# RadarControl_V1_00.net
KiCad netlist of a schematic drawn in Altium Designer
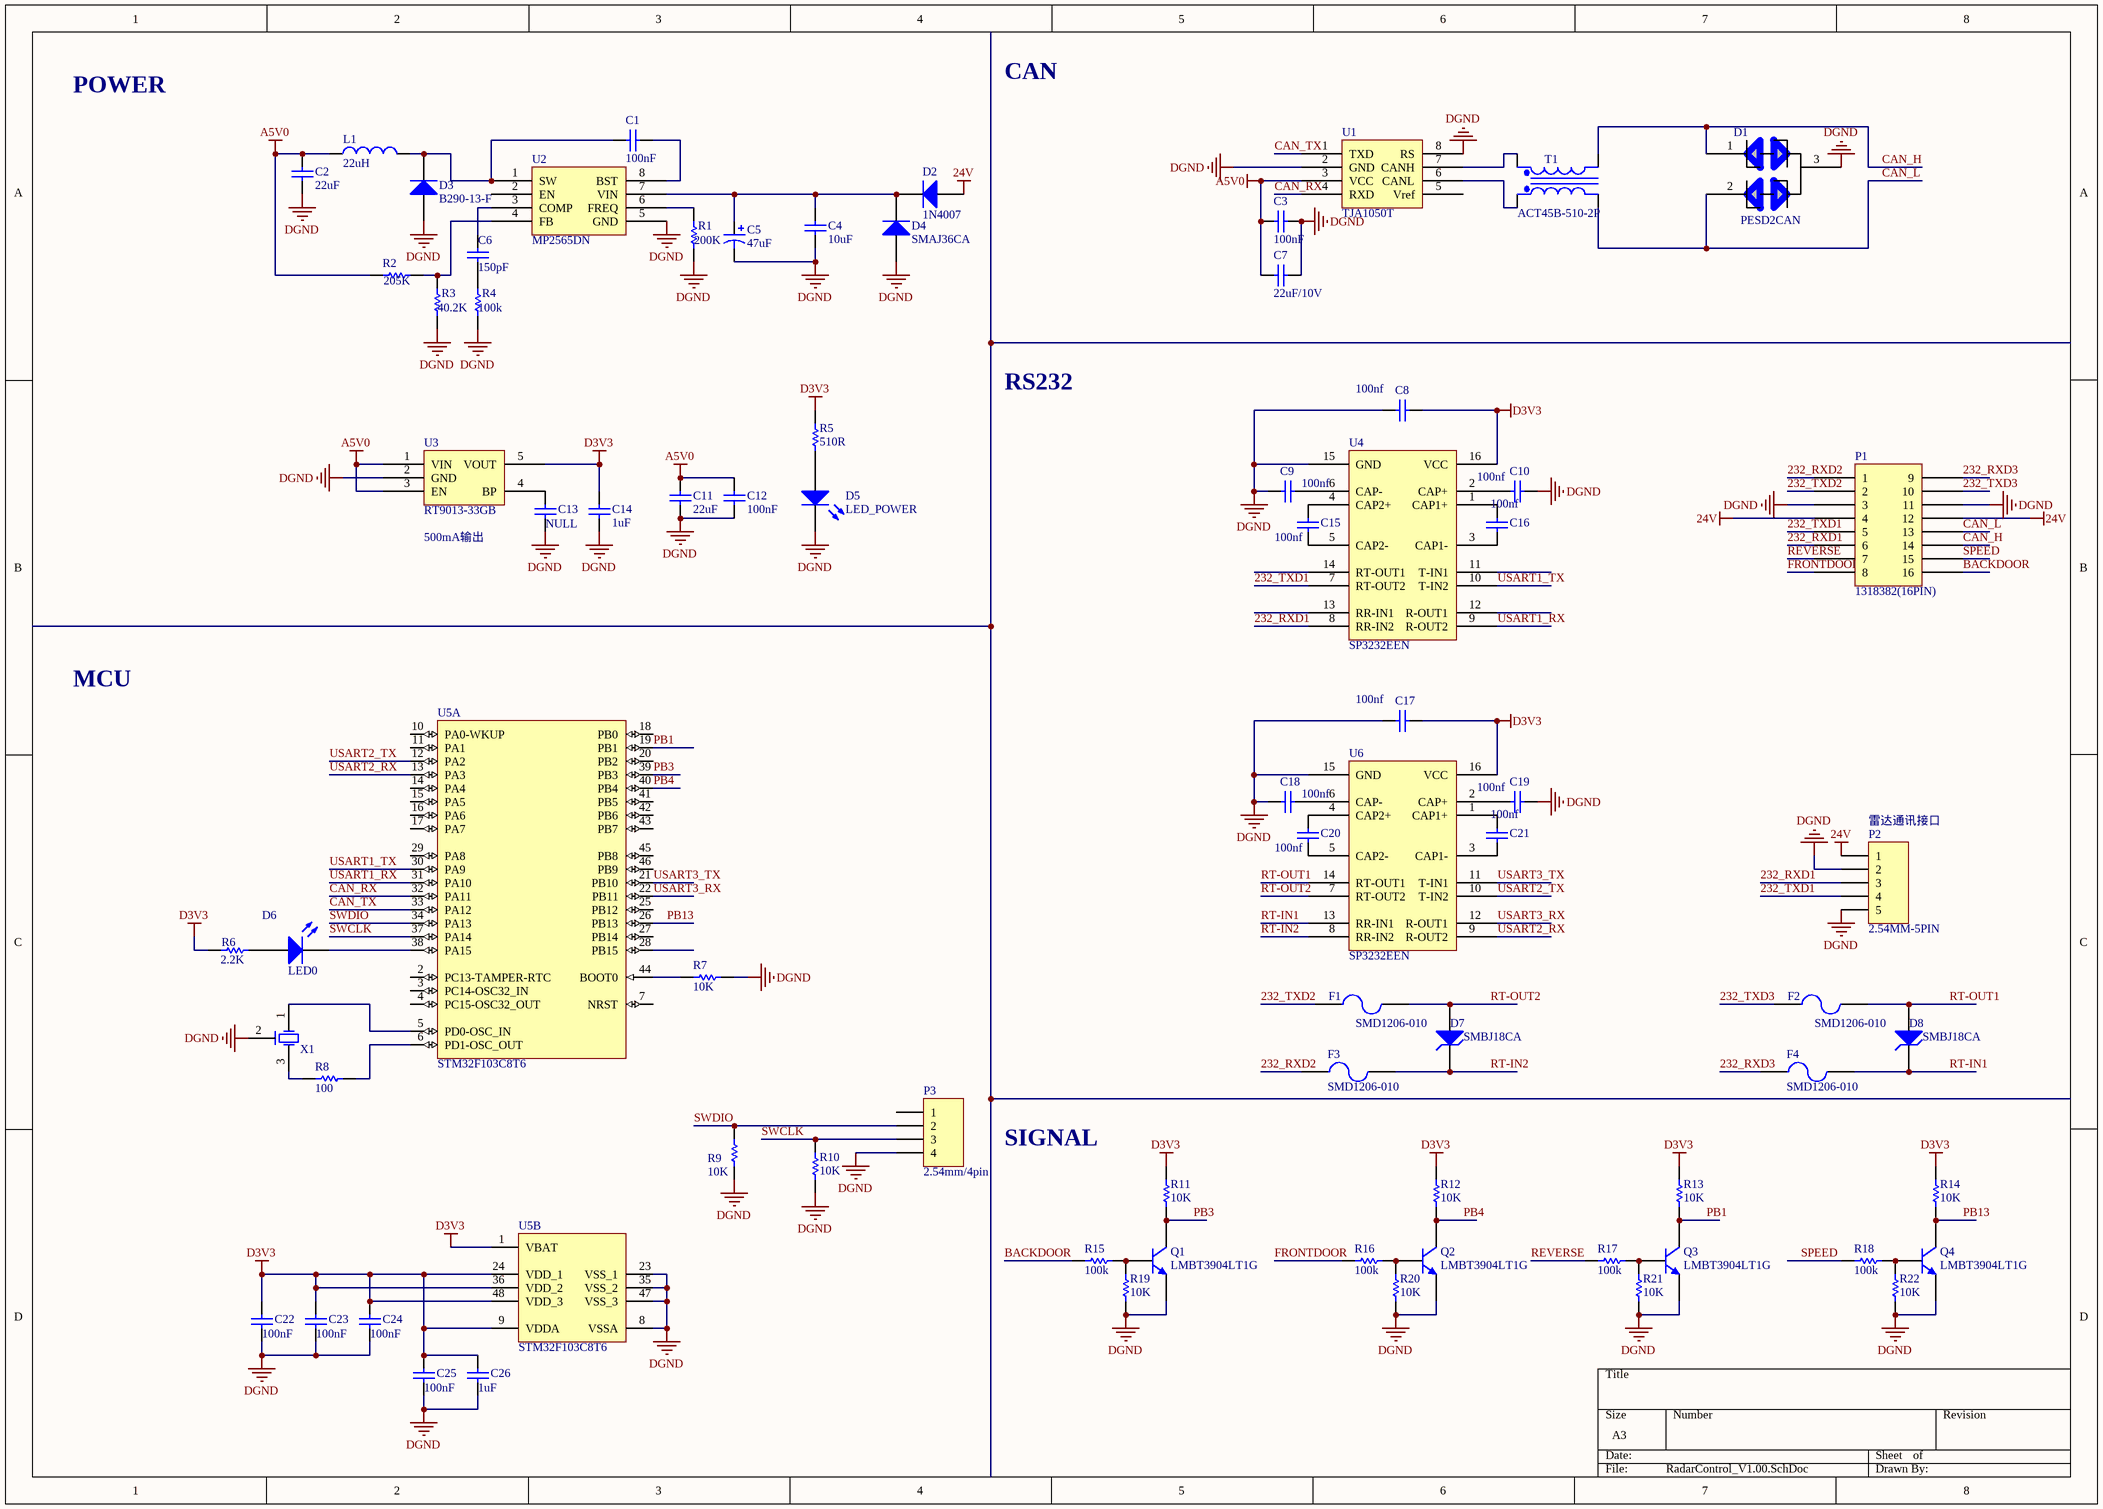
[diagram p0: RadarControl_V1.00.SchDoc]

(export (version "E")
  (design (tool "Eeschema 10.0.6"))
  (components
    (comp (ref "C1")
      (value "100nF")
      (footprint "0603")
      (description "Capacitor")
      (fields (field (name "PUBLISHER") "Altium Limited"))
      (libsource (lib "Miscellaneous Devices") (part "Cap"))
    )
    (comp (ref "C2")
      (value "22uF")
      (footprint "0805")
      (description "Capacitor,50V")
      (fields (field (name "PUBLISHER") "Altium Limited"))
      (libsource (lib "Miscellaneous Devices") (part "Cap"))
    )
    (comp (ref "C3")
      (value "100nF")
      (footprint "0603")
      (description "Capacitor")
      (fields (field (name "PUBLISHER") "Altium Limited"))
      (libsource (lib "Miscellaneous Devices") (part "Cap"))
    )
    (comp (ref "C4")
      (value "10uF")
      (footprint "0805")
      (description "Capacitor,50V")
      (fields (field (name "PUBLISHER") "Altium Limited"))
      (libsource (lib "Miscellaneous Devices") (part "Cap"))
    )
    (comp (ref "C5")
      (value "47uF")
      (footprint "cap_pol_8*10.2")
      (description "Polarized Capacitor (Radial)")
      (fields (field (name "PUBLISHER") "Altium Limited"))
      (libsource (lib "Miscellaneous Devices") (part "Cap Pol1"))
    )
    (comp (ref "C6")
      (value "150pF")
      (footprint "0603")
      (description "Capacitor")
      (fields (field (name "PUBLISHER") "Altium Limited"))
      (libsource (lib "Miscellaneous Devices") (part "Cap"))
    )
    (comp (ref "C7")
      (value "22uF/10V")
      (footprint "0603")
      (description "Capacitor")
      (fields (field (name "PUBLISHER") "Altium Limited"))
      (libsource (lib "Miscellaneous Devices") (part "Cap"))
    )
    (comp (ref "C8")
      (value "100nf")
      (footprint "0603")
      (description "Capacitor")
      (fields (field (name "PUBLISHER") "Altium Limited"))
      (libsource (lib "Miscellaneous Devices") (part "Cap"))
    )
    (comp (ref "C9")
      (value "100nf")
      (footprint "0603")
      (description "Capacitor")
      (fields (field (name "PUBLISHER") "Altium Limited"))
      (libsource (lib "Miscellaneous Devices") (part "Cap"))
    )
    (comp (ref "C10")
      (value "100nf")
      (footprint "0603")
      (description "Capacitor")
      (fields (field (name "PUBLISHER") "Altium Limited"))
      (libsource (lib "Miscellaneous Devices") (part "Cap"))
    )
    (comp (ref "C11")
      (value "22uF")
      (footprint "1206")
      (description "Capacitor")
      (fields (field (name "PUBLISHER") "Altium Limited"))
      (libsource (lib "Miscellaneous Devices") (part "Cap"))
    )
    (comp (ref "C12")
      (value "100nF")
      (footprint "0402")
      (description "Capacitor 5V")
      (fields (field (name "PUBLISHER") "Altium Limited"))
      (libsource (lib "Miscellaneous Devices") (part "Cap"))
    )
    (comp (ref "C13")
      (value "NULL")
      (footprint "0402")
      (description "Capacitor")
      (fields (field (name "PUBLISHER") "Altium Limited"))
      (libsource (lib "Miscellaneous Devices") (part "Cap"))
    )
    (comp (ref "C14")
      (value "1uF")
      (footprint "0402")
      (description "Capacitor 3V3")
      (fields (field (name "PUBLISHER") "Altium Limited"))
      (libsource (lib "Miscellaneous Devices") (part "Cap"))
    )
    (comp (ref "C15")
      (value "100nf")
      (footprint "0603")
      (description "Capacitor")
      (fields (field (name "PUBLISHER") "Altium Limited"))
      (libsource (lib "Miscellaneous Devices") (part "Cap"))
    )
    (comp (ref "C16")
      (value "100nf")
      (footprint "0603")
      (description "Capacitor")
      (fields (field (name "PUBLISHER") "Altium Limited"))
      (libsource (lib "Miscellaneous Devices") (part "Cap"))
    )
    (comp (ref "C17")
      (value "100nf")
      (footprint "0603")
      (description "Capacitor")
      (fields (field (name "PUBLISHER") "Altium Limited"))
      (libsource (lib "Miscellaneous Devices") (part "Cap"))
    )
    (comp (ref "C18")
      (value "100nf")
      (footprint "0603")
      (description "Capacitor")
      (fields (field (name "PUBLISHER") "Altium Limited"))
      (libsource (lib "Miscellaneous Devices") (part "Cap"))
    )
    (comp (ref "C19")
      (value "100nf")
      (footprint "0603")
      (description "Capacitor")
      (fields (field (name "PUBLISHER") "Altium Limited"))
      (libsource (lib "Miscellaneous Devices") (part "Cap"))
    )
    (comp (ref "C20")
      (value "100nf")
      (footprint "0603")
      (description "Capacitor")
      (fields (field (name "PUBLISHER") "Altium Limited"))
      (libsource (lib "Miscellaneous Devices") (part "Cap"))
    )
    (comp (ref "C21")
      (value "100nf")
      (footprint "0603")
      (description "Capacitor")
      (fields (field (name "PUBLISHER") "Altium Limited"))
      (libsource (lib "Miscellaneous Devices") (part "Cap"))
    )
    (comp (ref "C22")
      (value "100nF")
      (footprint "0603")
      (description "Capacitor")
      (fields (field (name "PUBLISHER") "Altium Limited"))
      (libsource (lib "Miscellaneous Devices") (part "Cap"))
    )
    (comp (ref "C23")
      (value "100nF")
      (footprint "0603")
      (description "Capacitor")
      (fields (field (name "PUBLISHER") "Altium Limited"))
      (libsource (lib "Miscellaneous Devices") (part "Cap"))
    )
    (comp (ref "C24")
      (value "100nF")
      (footprint "0603")
      (description "Capacitor")
      (fields (field (name "PUBLISHER") "Altium Limited"))
      (libsource (lib "Miscellaneous Devices") (part "Cap"))
    )
    (comp (ref "C25")
      (value "100nF")
      (footprint "0603")
      (description "Capacitor")
      (fields (field (name "PUBLISHER") "Altium Limited"))
      (libsource (lib "Miscellaneous Devices") (part "Cap"))
    )
    (comp (ref "C26")
      (value "1uF")
      (footprint "0603")
      (description "Capacitor")
      (fields (field (name "PUBLISHER") "Altium Limited"))
      (libsource (lib "Miscellaneous Devices") (part "Cap"))
    )
    (comp (ref "D1")
      (value "PESD2CAN")
      (footprint "SOT23")
      (libsource (lib "BinFeng_Connectors") (part "PESD1CAN"))
    )
    (comp (ref "D2")
      (value "1N4007")
      (footprint "6032_pol")
      (description "1 Amp General Purpose Rectifier")
      (fields (field (name "PUBLISHER") "Altium Limited"))
      (libsource (lib "Miscellaneous Devices") (part "Diode 1N4007"))
    )
    (comp (ref "D3")
      (value "B290-13-F")
      (footprint "B290")
      (description "Default Diode")
      (fields (field (name "PUBLISHER") "Altium Limited"))
      (libsource (lib "Miscellaneous Devices") (part "Diode"))
    )
    (comp (ref "D4")
      (value "SMAJ36CA")
      (footprint "B290")
      (description "1 Amp General Purpose Rectifier")
      (fields (field (name "PUBLISHER") "Altium Limited"))
      (libsource (lib "Miscellaneous Devices") (part "Diode 1N4007"))
    )
    (comp (ref "D5")
      (value "LED_POWER")
      (footprint "0805-LED")
      (description "Typical INFRARED GaAs LED")
      (fields (field (name "PUBLISHER") "Altium Limited"))
      (libsource (lib "Miscellaneous Devices") (part "LED0"))
    )
    (comp (ref "D6")
      (value "LED0")
      (footprint "0805-LED")
      (description "green LED")
      (fields (field (name "PUBLISHER") "Altium Limited"))
      (libsource (lib "Miscellaneous Devices") (part "LED0"))
    )
    (comp (ref "D7")
      (value "SMBJ18CA")
      (footprint "SMB")
      (description "Zener Diode")
      (fields (field (name "PUBLISHER") "Altium Limited"))
      (libsource (lib "Miscellaneous Devices") (part "D Zener"))
    )
    (comp (ref "D8")
      (value "SMBJ18CA")
      (footprint "SMB")
      (description "Zener Diode")
      (fields (field (name "PUBLISHER") "Altium Limited"))
      (libsource (lib "Miscellaneous Devices") (part "D Zener"))
    )
    (comp (ref "F1")
      (value "SMD1206-010")
      (footprint "1206")
      (description "Fuse")
      (fields (field (name "PUBLISHER") "Altium Limited"))
      (libsource (lib "Miscellaneous Devices") (part "Fuse 2"))
    )
    (comp (ref "F2")
      (value "SMD1206-010")
      (footprint "1206")
      (description "Fuse")
      (fields (field (name "PUBLISHER") "Altium Limited"))
      (libsource (lib "Miscellaneous Devices") (part "Fuse 2"))
    )
    (comp (ref "F3")
      (value "SMD1206-010")
      (footprint "1206")
      (description "Fuse")
      (fields (field (name "PUBLISHER") "Altium Limited"))
      (libsource (lib "Miscellaneous Devices") (part "Fuse 2"))
    )
    (comp (ref "F4")
      (value "SMD1206-010")
      (footprint "1206")
      (description "Fuse")
      (fields (field (name "PUBLISHER") "Altium Limited"))
      (libsource (lib "Miscellaneous Devices") (part "Fuse 2"))
    )
    (comp (ref "L1")
      (value "22uH")
      (footprint "10*10Inductor")
      (description "Inductor, 1A")
      (fields (field (name "PUBLISHER") "Altium Limited"))
      (libsource (lib "Miscellaneous Devices") (part "Inductor"))
    )
    (comp (ref "P1")
      (value "1318382(16PIN)")
      (footprint "16pin 1318382")
      (libsource (lib "16PIN") (part "16PIN"))
    )
    (comp (ref "P2")
      (value "2.54MM-5PIN")
      (footprint "HDR1X6")
      (description "Header, 5-Pin")
      (fields (field (name "PUBLISHER") "Altium Limited"))
      (libsource (lib "Miscellaneous Connectors") (part "Header 5"))
    )
    (comp (ref "P3")
      (value "2.54mm/4pin")
      (footprint "HDR1X4")
      (description "Header, 4-Pin")
      (fields (field (name "PUBLISHER") "Altium Limited"))
      (libsource (lib "Miscellaneous Connectors") (part "Header 4"))
    )
    (comp (ref "Q1")
      (value "LMBT3904LT1G")
      (footprint "LC-SOT-23(SOT-23-3)")
      (description "NPN General Purpose Amplifier")
      (fields (field (name "PUBLISHER") "Altium Limited"))
      (libsource (lib "Miscellaneous Devices") (part "2N3904"))
    )
    (comp (ref "Q2")
      (value "LMBT3904LT1G")
      (footprint "LC-SOT-23(SOT-23-3)")
      (description "NPN General Purpose Amplifier")
      (fields (field (name "PUBLISHER") "Altium Limited"))
      (libsource (lib "Miscellaneous Devices") (part "2N3904"))
    )
    (comp (ref "Q3")
      (value "LMBT3904LT1G")
      (footprint "LC-SOT-23(SOT-23-3)")
      (description "NPN General Purpose Amplifier")
      (fields (field (name "PUBLISHER") "Altium Limited"))
      (libsource (lib "Miscellaneous Devices") (part "2N3904"))
    )
    (comp (ref "Q4")
      (value "LMBT3904LT1G")
      (footprint "LC-SOT-23(SOT-23-3)")
      (description "NPN General Purpose Amplifier")
      (fields (field (name "PUBLISHER") "Altium Limited"))
      (libsource (lib "Miscellaneous Devices") (part "2N3904"))
    )
    (comp (ref "R1")
      (value "200K")
      (footprint "0402")
      (description "Resistor")
      (fields (field (name "PUBLISHER") "Altium Limited"))
      (libsource (lib "Miscellaneous Devices") (part "Res1"))
    )
    (comp (ref "R2")
      (value "205K")
      (footprint "0603")
      (description "Resistor")
      (fields (field (name "PUBLISHER") "Altium Limited"))
      (libsource (lib "Miscellaneous Devices") (part "Res1"))
    )
    (comp (ref "R3")
      (value "40.2K")
      (footprint "0603")
      (description "Resistor")
      (fields (field (name "PUBLISHER") "Altium Limited"))
      (libsource (lib "Miscellaneous Devices") (part "Res1"))
    )
    (comp (ref "R4")
      (value "100k")
      (footprint "0603")
      (description "Resistor")
      (fields (field (name "PUBLISHER") "Altium Limited"))
      (libsource (lib "Miscellaneous Devices") (part "Res1"))
    )
    (comp (ref "R5")
      (value "510R")
      (footprint "0603")
      (description "Resistor")
      (fields (field (name "PUBLISHER") "Altium Limited"))
      (libsource (lib "Miscellaneous Devices") (part "Res1"))
    )
    (comp (ref "R6")
      (value "2.2K")
      (footprint "0603")
      (description "Resistor")
      (fields (field (name "PUBLISHER") "Altium Limited"))
      (libsource (lib "Miscellaneous Devices") (part "Res1"))
    )
    (comp (ref "R7")
      (value "10K")
      (footprint "0603")
      (description "Resistor")
      (fields (field (name "PUBLISHER") "Altium Limited"))
      (libsource (lib "Miscellaneous Devices") (part "Res1"))
    )
    (comp (ref "R8")
      (value "100")
      (footprint "0603")
      (description "Resistor")
      (fields (field (name "PUBLISHER") "Altium Limited"))
      (libsource (lib "Miscellaneous Devices") (part "Res1"))
    )
    (comp (ref "R9")
      (value "10K")
      (footprint "0603")
      (description "Resistor")
      (fields (field (name "Comment") "1K") (field (name "PUBLISHER") "Altium Limited"))
      (libsource (lib "Miscellaneous Devices") (part "Res1"))
    )
    (comp (ref "R10")
      (value "10K")
      (footprint "0603")
      (description "Resistor")
      (fields (field (name "Comment") "1K") (field (name "PUBLISHER") "Altium Limited"))
      (libsource (lib "Miscellaneous Devices") (part "Res1"))
    )
    (comp (ref "R11")
      (value "10K")
      (footprint "0603")
      (description "Resistor")
      (fields (field (name "PUBLISHER") "Altium Limited"))
      (libsource (lib "Miscellaneous Devices") (part "Res1"))
    )
    (comp (ref "R12")
      (value "10K")
      (footprint "0603")
      (description "Resistor")
      (fields (field (name "PUBLISHER") "Altium Limited"))
      (libsource (lib "Miscellaneous Devices") (part "Res1"))
    )
    (comp (ref "R13")
      (value "10K")
      (footprint "0603")
      (description "Resistor")
      (fields (field (name "PUBLISHER") "Altium Limited"))
      (libsource (lib "Miscellaneous Devices") (part "Res1"))
    )
    (comp (ref "R14")
      (value "10K")
      (footprint "0603")
      (description "Resistor")
      (fields (field (name "PUBLISHER") "Altium Limited"))
      (libsource (lib "Miscellaneous Devices") (part "Res1"))
    )
    (comp (ref "R15")
      (value "100k")
      (footprint "0603")
      (description "Resistor")
      (fields (field (name "PUBLISHER") "Altium Limited"))
      (libsource (lib "Miscellaneous Devices") (part "Res1"))
    )
    (comp (ref "R16")
      (value "100k")
      (footprint "0603")
      (description "Resistor")
      (fields (field (name "PUBLISHER") "Altium Limited"))
      (libsource (lib "Miscellaneous Devices") (part "Res1"))
    )
    (comp (ref "R17")
      (value "100k")
      (footprint "0603")
      (description "Resistor")
      (fields (field (name "PUBLISHER") "Altium Limited"))
      (libsource (lib "Miscellaneous Devices") (part "Res1"))
    )
    (comp (ref "R18")
      (value "100k")
      (footprint "0603")
      (description "Resistor")
      (fields (field (name "PUBLISHER") "Altium Limited"))
      (libsource (lib "Miscellaneous Devices") (part "Res1"))
    )
    (comp (ref "R19")
      (value "10K")
      (footprint "0603")
      (description "Resistor")
      (fields (field (name "PUBLISHER") "Altium Limited"))
      (libsource (lib "Miscellaneous Devices") (part "Res1"))
    )
    (comp (ref "R20")
      (value "10K")
      (footprint "0603")
      (description "Resistor")
      (fields (field (name "PUBLISHER") "Altium Limited"))
      (libsource (lib "Miscellaneous Devices") (part "Res1"))
    )
    (comp (ref "R21")
      (value "10K")
      (footprint "0603")
      (description "Resistor")
      (fields (field (name "PUBLISHER") "Altium Limited"))
      (libsource (lib "Miscellaneous Devices") (part "Res1"))
    )
    (comp (ref "R22")
      (value "10K")
      (footprint "0603")
      (description "Resistor")
      (fields (field (name "PUBLISHER") "Altium Limited"))
      (libsource (lib "Miscellaneous Devices") (part "Res1"))
    )
    (comp (ref "T1")
      (value "ACT45B-510-2P")
      (footprint "ACT45B-510-2P")
      (description "Transformer (Equivalent Circuit Model)")
      (fields (field (name "PUBLISHER") "Altium Limited"))
      (libsource (lib "Miscellaneous Devices") (part "Trans Eq"))
    )
    (comp (ref "U1")
      (value "TJA1050T")
      (footprint "SO8")
      (description "CAN Tranceiver")
      (libsource (lib "BinFeng_IC") (part "TJA1050T"))
    )
    (comp (ref "U2")
      (value "MP2565DN")
      (footprint "so-8")
      (description "DCDC 4.5V~28V input 1.8V ~5V output low power")
      (libsource (lib "BinFeng_IC") (part "MP1584"))
    )
    (comp (ref "U3")
      (value "RT9013-33GB")
      (footprint "SOT-23-5")
      (libsource (lib "BinFeng_IC") (part "RT9193"))
    )
    (comp (ref "U4") (value "SP3232EEN") (footprint "SO-16") (libsource (lib "changyong") (part "MAX202")))
    (comp (ref "U5")
      (value "STM32F103C8T6")
      (footprint "STM-LQFP48_M")
      (libsource (lib "STMicroelectronics STM32 F1") (part "STM32F103C8T6"))
    )
    (comp (ref "U6") (value "SP3232EEN") (footprint "SO-16") (libsource (lib "changyong") (part "MAX202")))
    (comp (ref "X1") (value "8M smd") (footprint "8M") (libsource (lib "Schlib1") (part "8M smd")))
  )
  (nets
    (net (code "1") (name "/232_RXD1") (class "Default")
      (node (ref "P1") (pin "6") (pinfunction "6_6") (pintype "passive"))
      (node (ref "P2") (pin "3") (pinfunction "3_3") (pintype "passive"))
      (node (ref "U4") (pin "8") (pinfunction "RR-IN2_8") (pintype "passive"))
    )
    (net (code "2") (name "/232_RXD2") (class "Default")
      (node (ref "F3") (pin "1") (pinfunction "1_1") (pintype "passive"))
      (node (ref "P1") (pin "1") (pinfunction "1_1") (pintype "passive"))
    )
    (net (code "3") (name "/232_RXD3") (class "Default")
      (node (ref "F4") (pin "1") (pinfunction "1_1") (pintype "passive"))
      (node (ref "P1") (pin "9") (pinfunction "9_9") (pintype "passive"))
    )
    (net (code "4") (name "/232_TXD1") (class "Default")
      (node (ref "P1") (pin "5") (pinfunction "5_5") (pintype "passive"))
      (node (ref "P2") (pin "4") (pinfunction "4_4") (pintype "passive"))
      (node (ref "U4") (pin "7") (pinfunction "RT-OUT2_7") (pintype "passive"))
    )
    (net (code "5") (name "/232_TXD2") (class "Default")
      (node (ref "F1") (pin "1") (pinfunction "1_1") (pintype "passive"))
      (node (ref "P1") (pin "2") (pinfunction "2_2") (pintype "passive"))
    )
    (net (code "6") (name "/232_TXD3") (class "Default")
      (node (ref "F2") (pin "1") (pinfunction "1_1") (pintype "passive"))
      (node (ref "P1") (pin "10") (pinfunction "10_10") (pintype "passive"))
    )
    (net (code "7") (name "/BACKDOOR") (class "Default")
      (node (ref "P1") (pin "16") (pinfunction "16_16") (pintype "passive"))
      (node (ref "R15") (pin "2") (pinfunction "2_2") (pintype "passive"))
    )
    (net (code "8") (name "/CAN_H") (class "Default")
      (node (ref "D1") (pin "1") (pinfunction "11_1") (pintype "passive"))
      (node (ref "P1") (pin "14") (pinfunction "14_14") (pintype "passive"))
      (node (ref "T1") (pin "4") (pinfunction "Sec-_4") (pintype "passive"))
    )
    (net (code "9") (name "/CAN_L") (class "Default")
      (node (ref "D1") (pin "2") (pinfunction "12_2") (pintype "passive"))
      (node (ref "P1") (pin "13") (pinfunction "13_13") (pintype "passive"))
      (node (ref "T1") (pin "2") (pinfunction "Pri-_2") (pintype "passive"))
    )
    (net (code "10") (name "/CAN_RX") (class "Default")
      (node (ref "U1") (pin "4") (pinfunction "RXD_4") (pintype "passive"))
      (node (ref "U5") (pin "32") (pinfunction "PA11_32") (pintype "bidirectional"))
    )
    (net (code "11") (name "/CAN_TX") (class "Default")
      (node (ref "U1") (pin "1") (pinfunction "TXD_1") (pintype "passive"))
      (node (ref "U5") (pin "33") (pinfunction "PA12_33") (pintype "bidirectional"))
    )
    (net (code "12") (name "/FRONTDOOR") (class "Default")
      (node (ref "P1") (pin "8") (pinfunction "8_8") (pintype "passive"))
      (node (ref "R16") (pin "2") (pinfunction "2_2") (pintype "passive"))
    )
    (net (code "13") (name "/PB1") (class "Default")
      (node (ref "Q3") (pin "3") (pinfunction "C_3") (pintype "passive"))
      (node (ref "R13") (pin "1") (pinfunction "1_1") (pintype "passive"))
      (node (ref "U5") (pin "19") (pinfunction "PB1_19") (pintype "bidirectional"))
    )
    (net (code "14") (name "/PB3") (class "Default")
      (node (ref "Q1") (pin "3") (pinfunction "C_3") (pintype "passive"))
      (node (ref "R11") (pin "1") (pinfunction "1_1") (pintype "passive"))
      (node (ref "U5") (pin "39") (pinfunction "PB3_39") (pintype "bidirectional"))
    )
    (net (code "15") (name "/PB4") (class "Default")
      (node (ref "Q2") (pin "3") (pinfunction "C_3") (pintype "passive"))
      (node (ref "R12") (pin "1") (pinfunction "1_1") (pintype "passive"))
      (node (ref "U5") (pin "40") (pinfunction "PB4_40") (pintype "bidirectional"))
    )
    (net (code "16") (name "/PB13") (class "Default")
      (node (ref "Q4") (pin "3") (pinfunction "C_3") (pintype "passive"))
      (node (ref "R14") (pin "1") (pinfunction "1_1") (pintype "passive"))
      (node (ref "U5") (pin "26") (pinfunction "PB13_26") (pintype "bidirectional"))
    )
    (net (code "17") (name "/REVERSE") (class "Default")
      (node (ref "P1") (pin "7") (pinfunction "7_7") (pintype "passive"))
      (node (ref "R17") (pin "2") (pinfunction "2_2") (pintype "passive"))
    )
    (net (code "18") (name "/RT-IN1") (class "Default")
      (node (ref "D8") (pin "2") (pinfunction "K_2") (pintype "passive"))
      (node (ref "F4") (pin "2") (pinfunction "2_2") (pintype "passive"))
      (node (ref "U6") (pin "13") (pinfunction "RR-IN1_13") (pintype "passive"))
    )
    (net (code "19") (name "/RT-IN2") (class "Default")
      (node (ref "D7") (pin "2") (pinfunction "K_2") (pintype "passive"))
      (node (ref "F3") (pin "2") (pinfunction "2_2") (pintype "passive"))
      (node (ref "U6") (pin "8") (pinfunction "RR-IN2_8") (pintype "passive"))
    )
    (net (code "20") (name "/RT-OUT1") (class "Default")
      (node (ref "D8") (pin "1") (pinfunction "A_1") (pintype "passive"))
      (node (ref "F2") (pin "2") (pinfunction "2_2") (pintype "passive"))
      (node (ref "U6") (pin "14") (pinfunction "RT-OUT1_14") (pintype "passive"))
    )
    (net (code "21") (name "/RT-OUT2") (class "Default")
      (node (ref "D7") (pin "1") (pinfunction "A_1") (pintype "passive"))
      (node (ref "F1") (pin "2") (pinfunction "2_2") (pintype "passive"))
      (node (ref "U6") (pin "7") (pinfunction "RT-OUT2_7") (pintype "passive"))
    )
    (net (code "22") (name "/SPEED") (class "Default")
      (node (ref "P1") (pin "15") (pinfunction "15_15") (pintype "passive"))
      (node (ref "R18") (pin "2") (pinfunction "2_2") (pintype "passive"))
    )
    (net (code "23") (name "/SWCLK") (class "Default")
      (node (ref "P3") (pin "3") (pinfunction "3_3") (pintype "passive"))
      (node (ref "R10") (pin "1") (pinfunction "1_1") (pintype "passive"))
      (node (ref "U5") (pin "37") (pinfunction "PA14_37") (pintype "bidirectional"))
    )
    (net (code "24") (name "/SWDIO") (class "Default")
      (node (ref "P3") (pin "2") (pinfunction "2_2") (pintype "passive"))
      (node (ref "R9") (pin "1") (pinfunction "1_1") (pintype "passive"))
      (node (ref "U5") (pin "34") (pinfunction "PA13_34") (pintype "bidirectional"))
    )
    (net (code "25") (name "/USART1_RX") (class "Default")
      (node (ref "U4") (pin "9") (pinfunction "R-OUT2_9") (pintype "passive"))
      (node (ref "U5") (pin "31") (pinfunction "PA10_31") (pintype "bidirectional"))
    )
    (net (code "26") (name "/USART1_TX") (class "Default")
      (node (ref "U4") (pin "10") (pinfunction "T-IN2_10") (pintype "passive"))
      (node (ref "U5") (pin "30") (pinfunction "PA9_30") (pintype "bidirectional"))
    )
    (net (code "27") (name "/USART2_RX") (class "Default")
      (node (ref "U5") (pin "13") (pinfunction "PA3_13") (pintype "bidirectional"))
      (node (ref "U6") (pin "9") (pinfunction "R-OUT2_9") (pintype "passive"))
    )
    (net (code "28") (name "/USART2_TX") (class "Default")
      (node (ref "U5") (pin "12") (pinfunction "PA2_12") (pintype "bidirectional"))
      (node (ref "U6") (pin "10") (pinfunction "T-IN2_10") (pintype "passive"))
    )
    (net (code "29") (name "/USART3_RX") (class "Default")
      (node (ref "U5") (pin "22") (pinfunction "PB11_22") (pintype "bidirectional"))
      (node (ref "U6") (pin "12") (pinfunction "R-OUT1_12") (pintype "passive"))
    )
    (net (code "30") (name "/USART3_TX") (class "Default")
      (node (ref "U5") (pin "21") (pinfunction "PB10_21") (pintype "bidirectional"))
      (node (ref "U6") (pin "11") (pinfunction "T-IN1_11") (pintype "passive"))
    )
    (net (code "31") (name "24V") (class "Default")
      (node (ref "D2") (pin "1") (pinfunction "A_1") (pintype "passive"))
      (node (ref "P1") (pin "12") (pinfunction "12_12") (pintype "passive"))
      (node (ref "P1") (pin "4") (pinfunction "4_4") (pintype "passive"))
      (node (ref "P2") (pin "1") (pinfunction "1_1") (pintype "passive"))
    )
    (net (code "32") (name "A5V0") (class "Default")
      (node (ref "C11") (pin "1") (pinfunction "1_1") (pintype "passive"))
      (node (ref "C12") (pin "2") (pinfunction "2_2") (pintype "passive"))
      (node (ref "C2") (pin "2") (pinfunction "2_2") (pintype "passive"))
      (node (ref "C3") (pin "1") (pinfunction "1_1") (pintype "passive"))
      (node (ref "C7") (pin "1") (pinfunction "1_1") (pintype "passive"))
      (node (ref "L1") (pin "1") (pinfunction "1_1") (pintype "passive"))
      (node (ref "R2") (pin "2") (pinfunction "2_2") (pintype "passive"))
      (node (ref "U1") (pin "3") (pinfunction "VCC_3") (pintype "passive"))
      (node (ref "U3") (pin "1") (pinfunction "VIN_1") (pintype "passive"))
      (node (ref "U3") (pin "3") (pinfunction "EN_3") (pintype "passive"))
    )
    (net (code "33") (name "D3V3") (class "Default")
      (node (ref "C14") (pin "2") (pinfunction "2_2") (pintype "passive"))
      (node (ref "C17") (pin "2") (pinfunction "2_2") (pintype "passive"))
      (node (ref "C22") (pin "2") (pinfunction "2_2") (pintype "passive"))
      (node (ref "C23") (pin "2") (pinfunction "2_2") (pintype "passive"))
      (node (ref "C24") (pin "2") (pinfunction "2_2") (pintype "passive"))
      (node (ref "C25") (pin "2") (pinfunction "2_2") (pintype "passive"))
      (node (ref "C26") (pin "2") (pinfunction "2_2") (pintype "passive"))
      (node (ref "C8") (pin "2") (pinfunction "2_2") (pintype "passive"))
      (node (ref "R11") (pin "2") (pinfunction "2_2") (pintype "passive"))
      (node (ref "R12") (pin "2") (pinfunction "2_2") (pintype "passive"))
      (node (ref "R13") (pin "2") (pinfunction "2_2") (pintype "passive"))
      (node (ref "R14") (pin "2") (pinfunction "2_2") (pintype "passive"))
      (node (ref "R5") (pin "2") (pinfunction "2_2") (pintype "passive"))
      (node (ref "R6") (pin "2") (pinfunction "2_2") (pintype "passive"))
      (node (ref "U3") (pin "5") (pinfunction "VOUT_5") (pintype "passive"))
      (node (ref "U4") (pin "16") (pinfunction "VCC_16") (pintype "passive"))
      (node (ref "U5") (pin "1") (pinfunction "VBAT_1") (pintype "power_in"))
      (node (ref "U5") (pin "24") (pinfunction "VDD_1_24") (pintype "power_in"))
      (node (ref "U5") (pin "36") (pinfunction "VDD_2_36") (pintype "power_in"))
      (node (ref "U5") (pin "48") (pinfunction "VDD_3_48") (pintype "power_in"))
      (node (ref "U5") (pin "9") (pinfunction "VDDA_9") (pintype "power_in"))
      (node (ref "U6") (pin "16") (pinfunction "VCC_16") (pintype "passive"))
    )
    (net (code "34") (name "DGND") (class "Default")
      (node (ref "C10") (pin "1") (pinfunction "1_1") (pintype "passive"))
      (node (ref "C11") (pin "2") (pinfunction "2_2") (pintype "passive"))
      (node (ref "C12") (pin "1") (pinfunction "1_1") (pintype "passive"))
      (node (ref "C13") (pin "1") (pinfunction "1_1") (pintype "passive"))
      (node (ref "C14") (pin "1") (pinfunction "1_1") (pintype "passive"))
      (node (ref "C17") (pin "1") (pinfunction "1_1") (pintype "passive"))
      (node (ref "C18") (pin "1") (pinfunction "1_1") (pintype "passive"))
      (node (ref "C19") (pin "1") (pinfunction "1_1") (pintype "passive"))
      (node (ref "C2") (pin "1") (pinfunction "1_1") (pintype "passive"))
      (node (ref "C22") (pin "1") (pinfunction "1_1") (pintype "passive"))
      (node (ref "C23") (pin "1") (pinfunction "1_1") (pintype "passive"))
      (node (ref "C24") (pin "1") (pinfunction "1_1") (pintype "passive"))
      (node (ref "C25") (pin "1") (pinfunction "1_1") (pintype "passive"))
      (node (ref "C26") (pin "1") (pinfunction "1_1") (pintype "passive"))
      (node (ref "C3") (pin "2") (pinfunction "2_2") (pintype "passive"))
      (node (ref "C4") (pin "1") (pinfunction "1_1") (pintype "passive"))
      (node (ref "C5") (pin "2") (pinfunction "2_2") (pintype "passive"))
      (node (ref "C7") (pin "2") (pinfunction "2_2") (pintype "passive"))
      (node (ref "C8") (pin "1") (pinfunction "1_1") (pintype "passive"))
      (node (ref "C9") (pin "1") (pinfunction "1_1") (pintype "passive"))
      (node (ref "D1") (pin "3") (pinfunction "13_3") (pintype "passive"))
      (node (ref "D3") (pin "1") (pinfunction "A_1") (pintype "passive"))
      (node (ref "D4") (pin "1") (pinfunction "A_1") (pintype "passive"))
      (node (ref "D5") (pin "2") (pinfunction "K_2") (pintype "passive"))
      (node (ref "P1") (pin "11") (pinfunction "11_11") (pintype "passive"))
      (node (ref "P1") (pin "3") (pinfunction "3_3") (pintype "passive"))
      (node (ref "P2") (pin "2") (pinfunction "2_2") (pintype "passive"))
      (node (ref "P2") (pin "5") (pinfunction "5_5") (pintype "passive"))
      (node (ref "P3") (pin "4") (pinfunction "4_4") (pintype "passive"))
      (node (ref "Q1") (pin "1") (pinfunction "E_1") (pintype "passive"))
      (node (ref "Q2") (pin "1") (pinfunction "E_1") (pintype "passive"))
      (node (ref "Q3") (pin "1") (pinfunction "E_1") (pintype "passive"))
      (node (ref "Q4") (pin "1") (pinfunction "E_1") (pintype "passive"))
      (node (ref "R1") (pin "1") (pinfunction "1_1") (pintype "passive"))
      (node (ref "R10") (pin "2") (pinfunction "2_2") (pintype "passive"))
      (node (ref "R19") (pin "1") (pinfunction "1_1") (pintype "passive"))
      (node (ref "R20") (pin "1") (pinfunction "1_1") (pintype "passive"))
      (node (ref "R21") (pin "1") (pinfunction "1_1") (pintype "passive"))
      (node (ref "R22") (pin "1") (pinfunction "1_1") (pintype "passive"))
      (node (ref "R3") (pin "1") (pinfunction "1_1") (pintype "passive"))
      (node (ref "R4") (pin "1") (pinfunction "1_1") (pintype "passive"))
      (node (ref "R7") (pin "2") (pinfunction "2_2") (pintype "passive"))
      (node (ref "R9") (pin "2") (pinfunction "2_2") (pintype "passive"))
      (node (ref "U1") (pin "2") (pinfunction "GND_2") (pintype "passive"))
      (node (ref "U1") (pin "8") (pinfunction "RS_8") (pintype "passive"))
      (node (ref "U2") (pin "5") (pinfunction "GND_5") (pintype "passive"))
      (node (ref "U3") (pin "2") (pinfunction "GND_2") (pintype "passive"))
      (node (ref "U4") (pin "15") (pinfunction "GND_15") (pintype "passive"))
      (node (ref "U5") (pin "23") (pinfunction "VSS_1_23") (pintype "power_in"))
      (node (ref "U5") (pin "35") (pinfunction "VSS_2_35") (pintype "power_in"))
      (node (ref "U5") (pin "47") (pinfunction "VSS_3_47") (pintype "power_in"))
      (node (ref "U5") (pin "8") (pinfunction "VSSA_8") (pintype "power_in"))
      (node (ref "U6") (pin "15") (pinfunction "GND_15") (pintype "passive"))
      (node (ref "X1") (pin "2") (pinfunction "GND_2") (pintype "passive"))
    )
    (net (code "35") (name "Net-(C6-Pad2)") (class "Default")
      (node (ref "C6") (pin "2") (pinfunction "2_2") (pintype "passive"))
      (node (ref "R4") (pin "2") (pinfunction "2_2") (pintype "passive"))
    )
    (net (code "36") (name "Net-(D2-K)") (class "Default")
      (node (ref "C4") (pin "2") (pinfunction "2_2") (pintype "passive"))
      (node (ref "C5") (pin "1") (pinfunction "1_1") (pintype "passive"))
      (node (ref "D2") (pin "2") (pinfunction "K_2") (pintype "passive"))
      (node (ref "D4") (pin "2") (pinfunction "K_2") (pintype "passive"))
      (node (ref "U2") (pin "7") (pinfunction "VIN_7") (pintype "passive"))
    )
    (net (code "37") (name "Net-(D3-K)") (class "Default")
      (node (ref "C1") (pin "2") (pinfunction "2_2") (pintype "passive"))
      (node (ref "D3") (pin "2") (pinfunction "K_2") (pintype "passive"))
      (node (ref "L1") (pin "2") (pinfunction "2_2") (pintype "passive"))
      (node (ref "U2") (pin "1") (pinfunction "SW_1") (pintype "passive"))
    )
    (net (code "38") (name "Net-(D5-A)") (class "Default")
      (node (ref "D5") (pin "1") (pinfunction "A_1") (pintype "passive"))
      (node (ref "R5") (pin "1") (pinfunction "1_1") (pintype "passive"))
    )
    (net (code "39") (name "Net-(D6-A)") (class "Default")
      (node (ref "D6") (pin "1") (pinfunction "A_1") (pintype "passive"))
      (node (ref "R6") (pin "1") (pinfunction "1_1") (pintype "passive"))
    )
    (net (code "40") (name "Net-(D6-K)") (class "Default")
      (node (ref "D6") (pin "2") (pinfunction "K_2") (pintype "passive"))
      (node (ref "U5") (pin "38") (pinfunction "PA15_38") (pintype "bidirectional"))
    )
    (net (code "41") (name "Net-(Q1-B)") (class "Default")
      (node (ref "Q1") (pin "2") (pinfunction "B_2") (pintype "passive"))
      (node (ref "R15") (pin "1") (pinfunction "1_1") (pintype "passive"))
      (node (ref "R19") (pin "2") (pinfunction "2_2") (pintype "passive"))
    )
    (net (code "42") (name "Net-(Q2-B)") (class "Default")
      (node (ref "Q2") (pin "2") (pinfunction "B_2") (pintype "passive"))
      (node (ref "R16") (pin "1") (pinfunction "1_1") (pintype "passive"))
      (node (ref "R20") (pin "2") (pinfunction "2_2") (pintype "passive"))
    )
    (net (code "43") (name "Net-(Q3-B)") (class "Default")
      (node (ref "Q3") (pin "2") (pinfunction "B_2") (pintype "passive"))
      (node (ref "R17") (pin "1") (pinfunction "1_1") (pintype "passive"))
      (node (ref "R21") (pin "2") (pinfunction "2_2") (pintype "passive"))
    )
    (net (code "44") (name "Net-(Q4-B)") (class "Default")
      (node (ref "Q4") (pin "2") (pinfunction "B_2") (pintype "passive"))
      (node (ref "R18") (pin "1") (pinfunction "1_1") (pintype "passive"))
      (node (ref "R22") (pin "2") (pinfunction "2_2") (pintype "passive"))
    )
    (net (code "45") (name "Net-(T1-Pri+)") (class "Default")
      (node (ref "T1") (pin "1") (pinfunction "Pri+_1") (pintype "passive"))
      (node (ref "U1") (pin "6") (pinfunction "CANL_6") (pintype "passive"))
    )
    (net (code "46") (name "Net-(T1-Sec+)") (class "Default")
      (node (ref "T1") (pin "3") (pinfunction "Sec+_3") (pintype "passive"))
      (node (ref "U1") (pin "7") (pinfunction "CANH_7") (pintype "passive"))
    )
    (net (code "47") (name "Net-(U2-BST)") (class "Default")
      (node (ref "C1") (pin "1") (pinfunction "1_1") (pintype "passive"))
      (node (ref "U2") (pin "8") (pinfunction "BST_8") (pintype "passive"))
    )
    (net (code "48") (name "Net-(U2-COMP)") (class "Default")
      (node (ref "C6") (pin "1") (pinfunction "1_1") (pintype "passive"))
      (node (ref "U2") (pin "3") (pinfunction "COMP_3") (pintype "passive"))
    )
    (net (code "49") (name "Net-(U2-FB)") (class "Default")
      (node (ref "R2") (pin "1") (pinfunction "1_1") (pintype "passive"))
      (node (ref "R3") (pin "2") (pinfunction "2_2") (pintype "passive"))
      (node (ref "U2") (pin "4") (pinfunction "FB_4") (pintype "passive"))
    )
    (net (code "50") (name "Net-(U2-FREQ)") (class "Default")
      (node (ref "R1") (pin "2") (pinfunction "2_2") (pintype "passive"))
      (node (ref "U2") (pin "6") (pinfunction "FREQ_6") (pintype "passive"))
    )
    (net (code "51") (name "Net-(U3-BP)") (class "Default")
      (node (ref "C13") (pin "2") (pinfunction "2_2") (pintype "passive"))
      (node (ref "U3") (pin "4") (pinfunction "BP_4") (pintype "passive"))
    )
    (net (code "52") (name "Net-(U4-CAP+)") (class "Default")
      (node (ref "C10") (pin "2") (pinfunction "2_2") (pintype "passive"))
      (node (ref "U4") (pin "2") (pinfunction "CAP+_2") (pintype "passive"))
    )
    (net (code "53") (name "Net-(U4-CAP-)") (class "Default")
      (node (ref "C9") (pin "2") (pinfunction "2_2") (pintype "passive"))
      (node (ref "U4") (pin "6") (pinfunction "CAP-_6") (pintype "passive"))
    )
    (net (code "54") (name "Net-(U4-CAP1+)") (class "Default")
      (node (ref "C16") (pin "2") (pinfunction "2_2") (pintype "passive"))
      (node (ref "U4") (pin "1") (pinfunction "CAP1+_1") (pintype "passive"))
    )
    (net (code "55") (name "Net-(U4-CAP1-)") (class "Default")
      (node (ref "C16") (pin "1") (pinfunction "1_1") (pintype "passive"))
      (node (ref "U4") (pin "3") (pinfunction "CAP1-_3") (pintype "passive"))
    )
    (net (code "56") (name "Net-(U4-CAP2+)") (class "Default")
      (node (ref "C15") (pin "2") (pinfunction "2_2") (pintype "passive"))
      (node (ref "U4") (pin "4") (pinfunction "CAP2+_4") (pintype "passive"))
    )
    (net (code "57") (name "Net-(U4-CAP2-)") (class "Default")
      (node (ref "C15") (pin "1") (pinfunction "1_1") (pintype "passive"))
      (node (ref "U4") (pin "5") (pinfunction "CAP2-_5") (pintype "passive"))
    )
    (net (code "58") (name "Net-(U5A-BOOT0)") (class "Default")
      (node (ref "R7") (pin "1") (pinfunction "1_1") (pintype "passive"))
      (node (ref "U5") (pin "44") (pinfunction "BOOT0_44") (pintype "input"))
    )
    (net (code "59") (name "Net-(U5A-PD0-OSC_IN)") (class "Default")
      (node (ref "U5") (pin "5") (pinfunction "PD0-OSC_IN_5") (pintype "bidirectional"))
      (node (ref "X1") (pin "1") (pinfunction "OSC1_1") (pintype "passive"))
    )
    (net (code "60") (name "Net-(U5A-PD1-OSC_OUT)") (class "Default")
      (node (ref "R8") (pin "2") (pinfunction "2_2") (pintype "passive"))
      (node (ref "U5") (pin "6") (pinfunction "PD1-OSC_OUT_6") (pintype "bidirectional"))
    )
    (net (code "61") (name "Net-(U6-CAP+)") (class "Default")
      (node (ref "C19") (pin "2") (pinfunction "2_2") (pintype "passive"))
      (node (ref "U6") (pin "2") (pinfunction "CAP+_2") (pintype "passive"))
    )
    (net (code "62") (name "Net-(U6-CAP-)") (class "Default")
      (node (ref "C18") (pin "2") (pinfunction "2_2") (pintype "passive"))
      (node (ref "U6") (pin "6") (pinfunction "CAP-_6") (pintype "passive"))
    )
    (net (code "63") (name "Net-(U6-CAP1+)") (class "Default")
      (node (ref "C21") (pin "2") (pinfunction "2_2") (pintype "passive"))
      (node (ref "U6") (pin "1") (pinfunction "CAP1+_1") (pintype "passive"))
    )
    (net (code "64") (name "Net-(U6-CAP1-)") (class "Default")
      (node (ref "C21") (pin "1") (pinfunction "1_1") (pintype "passive"))
      (node (ref "U6") (pin "3") (pinfunction "CAP1-_3") (pintype "passive"))
    )
    (net (code "65") (name "Net-(U6-CAP2+)") (class "Default")
      (node (ref "C20") (pin "2") (pinfunction "2_2") (pintype "passive"))
      (node (ref "U6") (pin "4") (pinfunction "CAP2+_4") (pintype "passive"))
    )
    (net (code "66") (name "Net-(U6-CAP2-)") (class "Default")
      (node (ref "C20") (pin "1") (pinfunction "1_1") (pintype "passive"))
      (node (ref "U6") (pin "5") (pinfunction "CAP2-_5") (pintype "passive"))
    )
    (net (code "67") (name "Net-(X1-OSC2)") (class "Default")
      (node (ref "R8") (pin "1") (pinfunction "1_1") (pintype "passive"))
      (node (ref "X1") (pin "3") (pinfunction "OSC2_3") (pintype "passive"))
    )
    (net (code "68") (name "unconnected-(P3-Pad1)") (class "Default")
      (node (ref "P3") (pin "1") (pinfunction "1_1") (pintype "passive"))
    )
    (net (code "69") (name "unconnected-(U1-Vref-Pad5)") (class "Default")
      (node (ref "U1") (pin "5") (pinfunction "Vref_5") (pintype "passive"))
    )
    (net (code "70") (name "unconnected-(U2-EN-Pad2)") (class "Default")
      (node (ref "U2") (pin "2") (pinfunction "EN_2") (pintype "passive"))
    )
    (net (code "71") (name "unconnected-(U4-R-OUT1-Pad12)") (class "Default")
      (node (ref "U4") (pin "12") (pinfunction "R-OUT1_12") (pintype "passive"))
    )
    (net (code "72") (name "unconnected-(U4-RR-IN1-Pad13)") (class "Default")
      (node (ref "U4") (pin "13") (pinfunction "RR-IN1_13") (pintype "passive"))
    )
    (net (code "73") (name "unconnected-(U4-RT-OUT1-Pad14)") (class "Default")
      (node (ref "U4") (pin "14") (pinfunction "RT-OUT1_14") (pintype "passive"))
    )
    (net (code "74") (name "unconnected-(U4-T-IN1-Pad11)") (class "Default")
      (node (ref "U4") (pin "11") (pinfunction "T-IN1_11") (pintype "passive"))
    )
    (net (code "75") (name "unconnected-(U5A-NRST-Pad7)") (class "Default")
      (node (ref "U5") (pin "7") (pinfunction "NRST_7") (pintype "bidirectional"))
    )
    (net (code "76") (name "unconnected-(U5A-PA0-WKUP-Pad10)") (class "Default")
      (node (ref "U5") (pin "10") (pinfunction "PA0-WKUP_10") (pintype "bidirectional"))
    )
    (net (code "77") (name "unconnected-(U5A-PA1-Pad11)") (class "Default")
      (node (ref "U5") (pin "11") (pinfunction "PA1_11") (pintype "bidirectional"))
    )
    (net (code "78") (name "unconnected-(U5A-PA4-Pad14)") (class "Default")
      (node (ref "U5") (pin "14") (pinfunction "PA4_14") (pintype "bidirectional"))
    )
    (net (code "79") (name "unconnected-(U5A-PA5-Pad15)") (class "Default")
      (node (ref "U5") (pin "15") (pinfunction "PA5_15") (pintype "bidirectional"))
    )
    (net (code "80") (name "unconnected-(U5A-PA6-Pad16)") (class "Default")
      (node (ref "U5") (pin "16") (pinfunction "PA6_16") (pintype "bidirectional"))
    )
    (net (code "81") (name "unconnected-(U5A-PA7-Pad17)") (class "Default")
      (node (ref "U5") (pin "17") (pinfunction "PA7_17") (pintype "bidirectional"))
    )
    (net (code "82") (name "unconnected-(U5A-PA8-Pad29)") (class "Default")
      (node (ref "U5") (pin "29") (pinfunction "PA8_29") (pintype "bidirectional"))
    )
    (net (code "83") (name "unconnected-(U5A-PB0-Pad18)") (class "Default")
      (node (ref "U5") (pin "18") (pinfunction "PB0_18") (pintype "bidirectional"))
    )
    (net (code "84") (name "unconnected-(U5A-PB2-Pad20)") (class "Default")
      (node (ref "U5") (pin "20") (pinfunction "PB2_20") (pintype "bidirectional"))
    )
    (net (code "85") (name "unconnected-(U5A-PB5-Pad41)") (class "Default")
      (node (ref "U5") (pin "41") (pinfunction "PB5_41") (pintype "bidirectional"))
    )
    (net (code "86") (name "unconnected-(U5A-PB6-Pad42)") (class "Default")
      (node (ref "U5") (pin "42") (pinfunction "PB6_42") (pintype "bidirectional"))
    )
    (net (code "87") (name "unconnected-(U5A-PB7-Pad43)") (class "Default")
      (node (ref "U5") (pin "43") (pinfunction "PB7_43") (pintype "bidirectional"))
    )
    (net (code "88") (name "unconnected-(U5A-PB8-Pad45)") (class "Default")
      (node (ref "U5") (pin "45") (pinfunction "PB8_45") (pintype "bidirectional"))
    )
    (net (code "89") (name "unconnected-(U5A-PB9-Pad46)") (class "Default")
      (node (ref "U5") (pin "46") (pinfunction "PB9_46") (pintype "bidirectional"))
    )
    (net (code "90") (name "unconnected-(U5A-PB12-Pad25)") (class "Default")
      (node (ref "U5") (pin "25") (pinfunction "PB12_25") (pintype "bidirectional"))
    )
    (net (code "91") (name "unconnected-(U5A-PB14-Pad27)") (class "Default")
      (node (ref "U5") (pin "27") (pinfunction "PB14_27") (pintype "bidirectional"))
    )
    (net (code "92") (name "unconnected-(U5A-PB15-Pad28)") (class "Default")
      (node (ref "U5") (pin "28") (pinfunction "PB15_28") (pintype "bidirectional"))
    )
    (net (code "93") (name "unconnected-(U5A-PC13-TAMPER-RTC-Pad2)") (class "Default")
      (node (ref "U5") (pin "2") (pinfunction "PC13-TAMPER-RTC_2") (pintype "bidirectional"))
    )
    (net (code "94") (name "unconnected-(U5A-PC14-OSC32_IN-Pad3)") (class "Default")
      (node (ref "U5") (pin "3") (pinfunction "PC14-OSC32_IN_3") (pintype "bidirectional"))
    )
    (net (code "95") (name "unconnected-(U5A-PC15-OSC32_OUT-Pad4)") (class "Default")
      (node (ref "U5") (pin "4") (pinfunction "PC15-OSC32_OUT_4") (pintype "bidirectional"))
    )
  )
)
